# MB997.net
KiCad netlist of a schematic drawn in Altium Designer
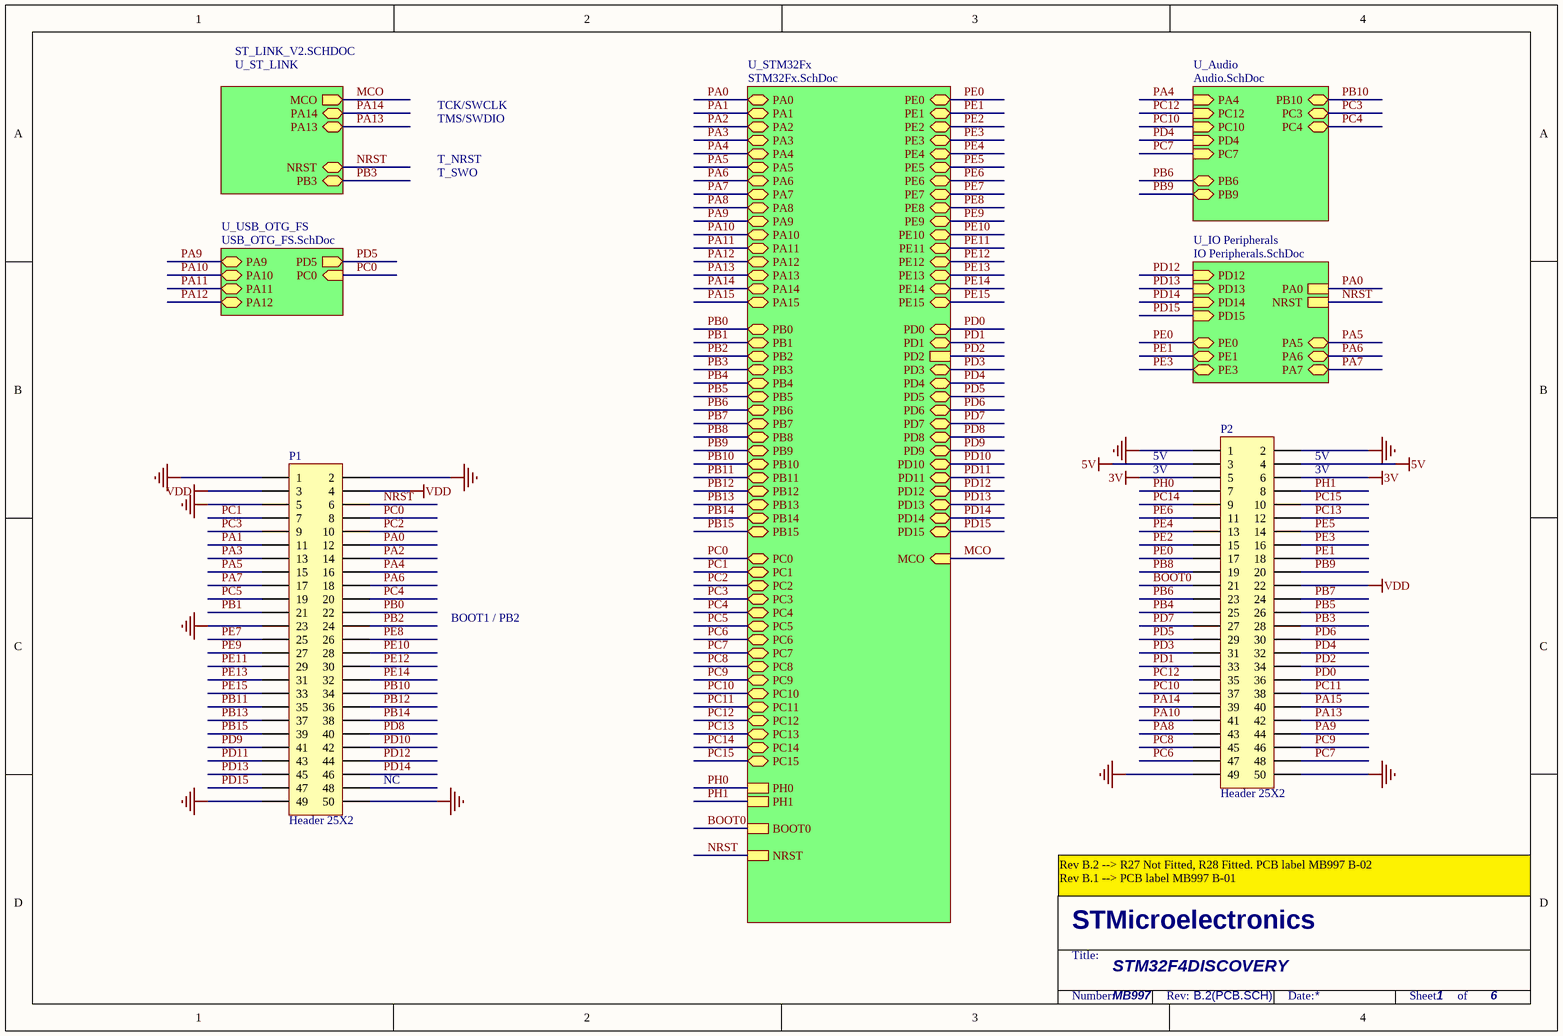
[diagram p0: MB997.SchDoc]

(export (version "E")
  (design (tool "Eeschema 10.0.6"))
  (components
    (comp (ref "P1")
      (value "Header 25X2")
      (footprint "HDR2X25")
      (description "Header, 25-Pin, Dual row")
      (fields (field (name "PUBLISHER") "Altium Limited"))
      (libsource (lib "Miscellaneous Connectors") (part "Header 25X2"))
    )
    (comp (ref "P2")
      (value "Header 25X2")
      (footprint "HDR2X25")
      (description "Header, 25-Pin, Dual row")
      (fields (field (name "PUBLISHER") "Altium Limited"))
      (libsource (lib "Miscellaneous Connectors") (part "Header 25X2"))
    )
  )
  (nets
    (net (code "1") (name "/BOOT0") (class "Default")
      (node (ref "P2") (pin "21") (pinfunction "21_21") (pintype "passive"))
    )
    (net (code "3") (name "/NRST") (class "Default")
      (node (ref "P1") (pin "6") (pinfunction "6_6") (pintype "passive"))
    )
    (net (code "4") (name "/PA0") (class "Default")
      (node (ref "P1") (pin "12") (pinfunction "12_12") (pintype "passive"))
    )
    (net (code "5") (name "/PA1") (class "Default")
      (node (ref "P1") (pin "11") (pinfunction "11_11") (pintype "passive"))
    )
    (net (code "6") (name "/PA2") (class "Default")
      (node (ref "P1") (pin "14") (pinfunction "14_14") (pintype "passive"))
    )
    (net (code "7") (name "/PA3") (class "Default")
      (node (ref "P1") (pin "13") (pinfunction "13_13") (pintype "passive"))
    )
    (net (code "8") (name "/PA4") (class "Default")
      (node (ref "P1") (pin "16") (pinfunction "16_16") (pintype "passive"))
    )
    (net (code "9") (name "/PA5") (class "Default")
      (node (ref "P1") (pin "15") (pinfunction "15_15") (pintype "passive"))
    )
    (net (code "10") (name "/PA6") (class "Default")
      (node (ref "P1") (pin "18") (pinfunction "18_18") (pintype "passive"))
    )
    (net (code "11") (name "/PA7") (class "Default")
      (node (ref "P1") (pin "17") (pinfunction "17_17") (pintype "passive"))
    )
    (net (code "12") (name "/PA8") (class "Default")
      (node (ref "P2") (pin "43") (pinfunction "43_43") (pintype "passive"))
    )
    (net (code "13") (name "/PA9") (class "Default")
      (node (ref "P2") (pin "44") (pinfunction "44_44") (pintype "passive"))
    )
    (net (code "14") (name "/PA10") (class "Default")
      (node (ref "P2") (pin "41") (pinfunction "41_41") (pintype "passive"))
    )
    (net (code "17") (name "/PA13") (class "Default")
      (node (ref "P2") (pin "42") (pinfunction "42_42") (pintype "passive"))
    )
    (net (code "18") (name "/PA14") (class "Default")
      (node (ref "P2") (pin "39") (pinfunction "39_39") (pintype "passive"))
    )
    (net (code "19") (name "/PA15") (class "Default")
      (node (ref "P2") (pin "40") (pinfunction "40_40") (pintype "passive"))
    )
    (net (code "20") (name "/PB0") (class "Default")
      (node (ref "P1") (pin "22") (pinfunction "22_22") (pintype "passive"))
    )
    (net (code "21") (name "/PB1") (class "Default")
      (node (ref "P1") (pin "21") (pinfunction "21_21") (pintype "passive"))
    )
    (net (code "22") (name "/PB2") (class "Default")
      (node (ref "P1") (pin "24") (pinfunction "24_24") (pintype "passive"))
    )
    (net (code "23") (name "/PB3") (class "Default")
      (node (ref "P2") (pin "28") (pinfunction "28_28") (pintype "passive"))
    )
    (net (code "24") (name "/PB4") (class "Default")
      (node (ref "P2") (pin "25") (pinfunction "25_25") (pintype "passive"))
    )
    (net (code "25") (name "/PB5") (class "Default")
      (node (ref "P2") (pin "26") (pinfunction "26_26") (pintype "passive"))
    )
    (net (code "26") (name "/PB6") (class "Default")
      (node (ref "P2") (pin "23") (pinfunction "23_23") (pintype "passive"))
    )
    (net (code "27") (name "/PB7") (class "Default")
      (node (ref "P2") (pin "24") (pinfunction "24_24") (pintype "passive"))
    )
    (net (code "28") (name "/PB8") (class "Default")
      (node (ref "P2") (pin "19") (pinfunction "19_19") (pintype "passive"))
    )
    (net (code "29") (name "/PB9") (class "Default")
      (node (ref "P2") (pin "20") (pinfunction "20_20") (pintype "passive"))
    )
    (net (code "30") (name "/PB10") (class "Default")
      (node (ref "P1") (pin "34") (pinfunction "34_34") (pintype "passive"))
    )
    (net (code "31") (name "/PB11") (class "Default")
      (node (ref "P1") (pin "35") (pinfunction "35_35") (pintype "passive"))
    )
    (net (code "32") (name "/PB12") (class "Default")
      (node (ref "P1") (pin "36") (pinfunction "36_36") (pintype "passive"))
    )
    (net (code "33") (name "/PB13") (class "Default")
      (node (ref "P1") (pin "37") (pinfunction "37_37") (pintype "passive"))
    )
    (net (code "34") (name "/PB14") (class "Default")
      (node (ref "P1") (pin "38") (pinfunction "38_38") (pintype "passive"))
    )
    (net (code "35") (name "/PB15") (class "Default")
      (node (ref "P1") (pin "39") (pinfunction "39_39") (pintype "passive"))
    )
    (net (code "36") (name "/PC0") (class "Default")
      (node (ref "P1") (pin "8") (pinfunction "8_8") (pintype "passive"))
    )
    (net (code "37") (name "/PC1") (class "Default")
      (node (ref "P1") (pin "7") (pinfunction "7_7") (pintype "passive"))
    )
    (net (code "38") (name "/PC2") (class "Default")
      (node (ref "P1") (pin "10") (pinfunction "10_10") (pintype "passive"))
    )
    (net (code "39") (name "/PC3") (class "Default")
      (node (ref "P1") (pin "9") (pinfunction "9_9") (pintype "passive"))
    )
    (net (code "40") (name "/PC4") (class "Default")
      (node (ref "P1") (pin "20") (pinfunction "20_20") (pintype "passive"))
    )
    (net (code "41") (name "/PC5") (class "Default")
      (node (ref "P1") (pin "19") (pinfunction "19_19") (pintype "passive"))
    )
    (net (code "42") (name "/PC6") (class "Default")
      (node (ref "P2") (pin "47") (pinfunction "47_47") (pintype "passive"))
    )
    (net (code "43") (name "/PC7") (class "Default")
      (node (ref "P2") (pin "48") (pinfunction "48_48") (pintype "passive"))
    )
    (net (code "44") (name "/PC8") (class "Default")
      (node (ref "P2") (pin "45") (pinfunction "45_45") (pintype "passive"))
    )
    (net (code "45") (name "/PC9") (class "Default")
      (node (ref "P2") (pin "46") (pinfunction "46_46") (pintype "passive"))
    )
    (net (code "46") (name "/PC10") (class "Default")
      (node (ref "P2") (pin "37") (pinfunction "37_37") (pintype "passive"))
    )
    (net (code "47") (name "/PC11") (class "Default")
      (node (ref "P2") (pin "38") (pinfunction "38_38") (pintype "passive"))
    )
    (net (code "48") (name "/PC12") (class "Default")
      (node (ref "P2") (pin "35") (pinfunction "35_35") (pintype "passive"))
    )
    (net (code "49") (name "/PC13") (class "Default")
      (node (ref "P2") (pin "12") (pinfunction "12_12") (pintype "passive"))
    )
    (net (code "50") (name "/PC14") (class "Default")
      (node (ref "P2") (pin "9") (pinfunction "9_9") (pintype "passive"))
    )
    (net (code "51") (name "/PC15") (class "Default")
      (node (ref "P2") (pin "10") (pinfunction "10_10") (pintype "passive"))
    )
    (net (code "52") (name "/PD0") (class "Default")
      (node (ref "P2") (pin "36") (pinfunction "36_36") (pintype "passive"))
    )
    (net (code "53") (name "/PD1") (class "Default")
      (node (ref "P2") (pin "33") (pinfunction "33_33") (pintype "passive"))
    )
    (net (code "54") (name "/PD2") (class "Default")
      (node (ref "P2") (pin "34") (pinfunction "34_34") (pintype "passive"))
    )
    (net (code "55") (name "/PD3") (class "Default")
      (node (ref "P2") (pin "31") (pinfunction "31_31") (pintype "passive"))
    )
    (net (code "56") (name "/PD4") (class "Default")
      (node (ref "P2") (pin "32") (pinfunction "32_32") (pintype "passive"))
    )
    (net (code "57") (name "/PD5") (class "Default")
      (node (ref "P2") (pin "29") (pinfunction "29_29") (pintype "passive"))
    )
    (net (code "58") (name "/PD6") (class "Default")
      (node (ref "P2") (pin "30") (pinfunction "30_30") (pintype "passive"))
    )
    (net (code "59") (name "/PD7") (class "Default")
      (node (ref "P2") (pin "27") (pinfunction "27_27") (pintype "passive"))
    )
    (net (code "60") (name "/PD8") (class "Default")
      (node (ref "P1") (pin "40") (pinfunction "40_40") (pintype "passive"))
    )
    (net (code "61") (name "/PD9") (class "Default")
      (node (ref "P1") (pin "41") (pinfunction "41_41") (pintype "passive"))
    )
    (net (code "62") (name "/PD10") (class "Default")
      (node (ref "P1") (pin "42") (pinfunction "42_42") (pintype "passive"))
    )
    (net (code "63") (name "/PD11") (class "Default")
      (node (ref "P1") (pin "43") (pinfunction "43_43") (pintype "passive"))
    )
    (net (code "64") (name "/PD12") (class "Default")
      (node (ref "P1") (pin "44") (pinfunction "44_44") (pintype "passive"))
    )
    (net (code "65") (name "/PD13") (class "Default")
      (node (ref "P1") (pin "45") (pinfunction "45_45") (pintype "passive"))
    )
    (net (code "66") (name "/PD14") (class "Default")
      (node (ref "P1") (pin "46") (pinfunction "46_46") (pintype "passive"))
    )
    (net (code "67") (name "/PD15") (class "Default")
      (node (ref "P1") (pin "47") (pinfunction "47_47") (pintype "passive"))
    )
    (net (code "68") (name "/PE0") (class "Default")
      (node (ref "P2") (pin "17") (pinfunction "17_17") (pintype "passive"))
    )
    (net (code "69") (name "/PE1") (class "Default")
      (node (ref "P2") (pin "18") (pinfunction "18_18") (pintype "passive"))
    )
    (net (code "70") (name "/PE2") (class "Default")
      (node (ref "P2") (pin "15") (pinfunction "15_15") (pintype "passive"))
    )
    (net (code "71") (name "/PE3") (class "Default")
      (node (ref "P2") (pin "16") (pinfunction "16_16") (pintype "passive"))
    )
    (net (code "72") (name "/PE4") (class "Default")
      (node (ref "P2") (pin "13") (pinfunction "13_13") (pintype "passive"))
    )
    (net (code "73") (name "/PE5") (class "Default")
      (node (ref "P2") (pin "14") (pinfunction "14_14") (pintype "passive"))
    )
    (net (code "74") (name "/PE6") (class "Default")
      (node (ref "P2") (pin "11") (pinfunction "11_11") (pintype "passive"))
    )
    (net (code "75") (name "/PE7") (class "Default")
      (node (ref "P1") (pin "25") (pinfunction "25_25") (pintype "passive"))
    )
    (net (code "76") (name "/PE8") (class "Default")
      (node (ref "P1") (pin "26") (pinfunction "26_26") (pintype "passive"))
    )
    (net (code "77") (name "/PE9") (class "Default")
      (node (ref "P1") (pin "27") (pinfunction "27_27") (pintype "passive"))
    )
    (net (code "78") (name "/PE10") (class "Default")
      (node (ref "P1") (pin "28") (pinfunction "28_28") (pintype "passive"))
    )
    (net (code "79") (name "/PE11") (class "Default")
      (node (ref "P1") (pin "29") (pinfunction "29_29") (pintype "passive"))
    )
    (net (code "80") (name "/PE12") (class "Default")
      (node (ref "P1") (pin "30") (pinfunction "30_30") (pintype "passive"))
    )
    (net (code "81") (name "/PE13") (class "Default")
      (node (ref "P1") (pin "31") (pinfunction "31_31") (pintype "passive"))
    )
    (net (code "82") (name "/PE14") (class "Default")
      (node (ref "P1") (pin "32") (pinfunction "32_32") (pintype "passive"))
    )
    (net (code "83") (name "/PE15") (class "Default")
      (node (ref "P1") (pin "33") (pinfunction "33_33") (pintype "passive"))
    )
    (net (code "84") (name "/PH0") (class "Default")
      (node (ref "P2") (pin "7") (pinfunction "7_7") (pintype "passive"))
    )
    (net (code "85") (name "/PH1") (class "Default")
      (node (ref "P2") (pin "8") (pinfunction "8_8") (pintype "passive"))
    )
    (net (code "86") (name "3V") (class "Default")
      (node (ref "P2") (pin "5") (pinfunction "5_5") (pintype "passive"))
      (node (ref "P2") (pin "6") (pinfunction "6_6") (pintype "passive"))
    )
    (net (code "87") (name "5V") (class "Default")
      (node (ref "P2") (pin "3") (pinfunction "3_3") (pintype "passive"))
      (node (ref "P2") (pin "4") (pinfunction "4_4") (pintype "passive"))
    )
    (net (code "88") (name "GND") (class "Default")
      (node (ref "P1") (pin "1") (pinfunction "1_1") (pintype "passive"))
      (node (ref "P1") (pin "2") (pinfunction "2_2") (pintype "passive"))
      (node (ref "P1") (pin "23") (pinfunction "23_23") (pintype "passive"))
      (node (ref "P1") (pin "49") (pinfunction "49_49") (pintype "passive"))
      (node (ref "P1") (pin "5") (pinfunction "5_5") (pintype "passive"))
      (node (ref "P1") (pin "50") (pinfunction "50_50") (pintype "passive"))
      (node (ref "P2") (pin "1") (pinfunction "1_1") (pintype "passive"))
      (node (ref "P2") (pin "2") (pinfunction "2_2") (pintype "passive"))
      (node (ref "P2") (pin "49") (pinfunction "49_49") (pintype "passive"))
      (node (ref "P2") (pin "50") (pinfunction "50_50") (pintype "passive"))
    )
    (net (code "89") (name "VDD") (class "Default")
      (node (ref "P1") (pin "3") (pinfunction "3_3") (pintype "passive"))
      (node (ref "P1") (pin "4") (pinfunction "4_4") (pintype "passive"))
      (node (ref "P2") (pin "22") (pinfunction "22_22") (pintype "passive"))
    )
    (net (code "90") (name "unconnected-(P1-Pad48)") (class "Default")
      (node (ref "P1") (pin "48") (pinfunction "48_48") (pintype "passive"))
    )
  )
)
